# LightBoard.net
KiCad netlist of a schematic drawn in EAGLE
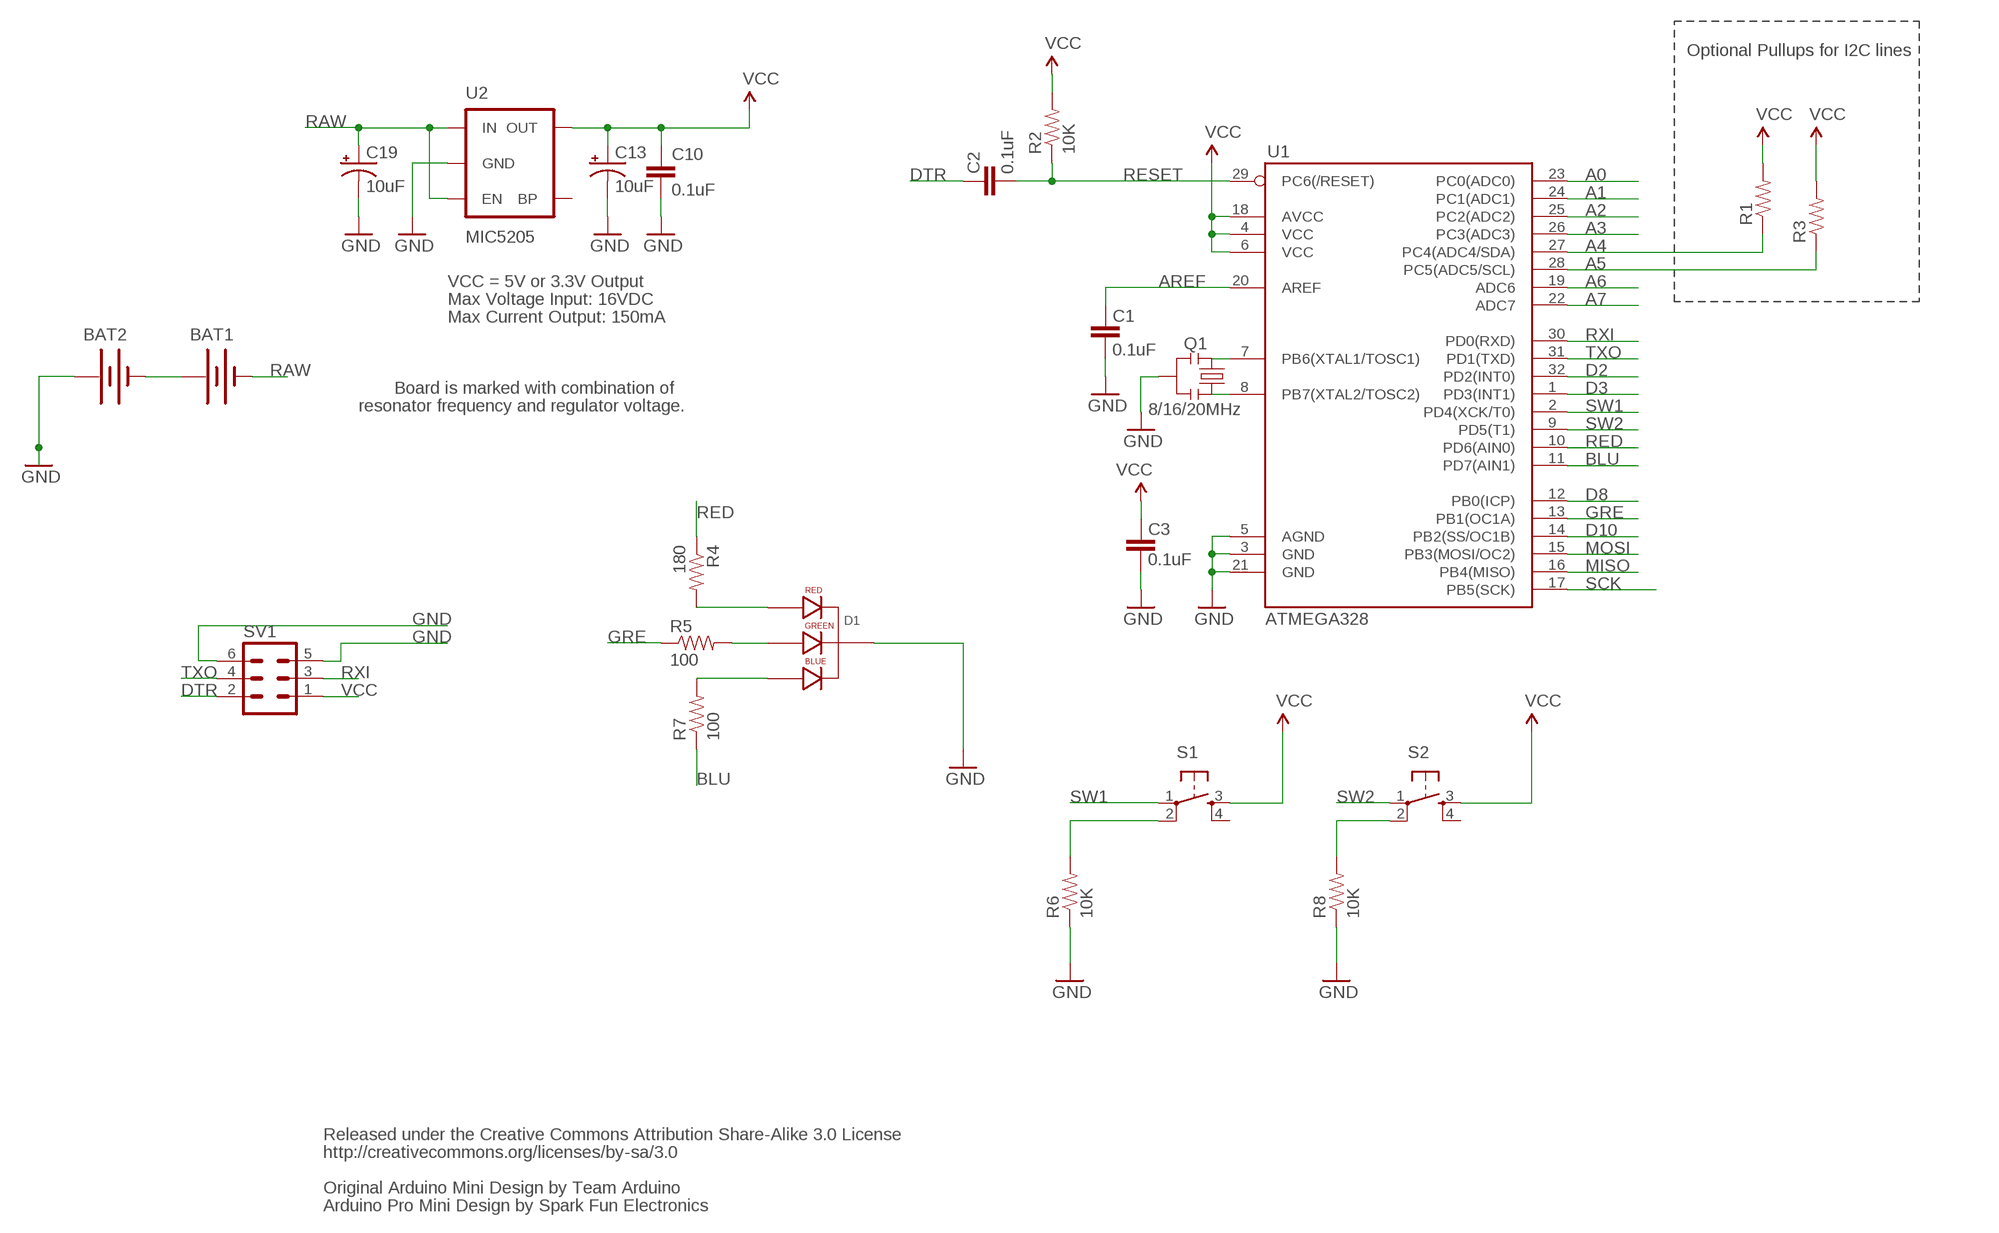
[diagram p0: schematic, sheet 1]

(export (version "E")
  (design (tool "Eeschema 10.0.6"))
  (components
    (comp (ref "BAT1")
      (value "BATTERY12MM")
      (footprint "eagle-import:BATTCON_12MM")
      (libsource (lib "eagle-import") (part "BATTERY12MM"))
    )
    (comp (ref "BAT2")
      (value "BATTERY12MM")
      (footprint "eagle-import:BATTCON_12MM")
      (libsource (lib "eagle-import") (part "BATTERY12MM"))
    )
    (comp (ref "C1")
      (value "0.1uF")
      (footprint "eagle-import:0402-CAP")
      (libsource (lib "eagle-import") (part "CAP0402-CAP"))
    )
    (comp (ref "C2")
      (value "0.1uF")
      (footprint "eagle-import:0402-CAP")
      (libsource (lib "eagle-import") (part "CAP0402-CAP"))
    )
    (comp (ref "C3")
      (value "0.1uF")
      (footprint "eagle-import:0402-CAP")
      (libsource (lib "eagle-import") (part "CAP0402-CAP"))
    )
    (comp (ref "C10")
      (value "0.1uF")
      (footprint "eagle-import:0402-CAP")
      (libsource (lib "eagle-import") (part "CAP0402-CAP"))
    )
    (comp (ref "C13")
      (value "10uF")
      (footprint "eagle-import:EIA3216")
      (libsource (lib "eagle-import") (part "CAP_POL1206"))
    )
    (comp (ref "C19")
      (value "10uF")
      (footprint "eagle-import:EIA3216")
      (libsource (lib "eagle-import") (part "CAP_POL1206"))
    )
    (comp (ref "D1")
      (value "LED-RGB-CC-THRUDIFFUSE")
      (footprint "eagle-import:LED-RGB-THRU")
      (libsource (lib "eagle-import") (part "LED-RGB-CC-THRUDIFFUSE"))
    )
    (comp (ref "Q1")
      (value "8/16/20MHz")
      (footprint "eagle-import:RESONATOR-SMD")
      (libsource (lib "eagle-import") (part "RESONATORSMD"))
    )
    (comp (ref "R1")
      (value "RESISTOR0402-RES")
      (footprint "eagle-import:0402-RES")
      (libsource (lib "eagle-import") (part "RESISTOR0402-RES"))
    )
    (comp (ref "R2")
      (value "10K")
      (footprint "eagle-import:0402-RES")
      (libsource (lib "eagle-import") (part "RESISTOR0402-RES"))
    )
    (comp (ref "R3")
      (value "RESISTOR0402-RES")
      (footprint "eagle-import:0402-RES")
      (libsource (lib "eagle-import") (part "RESISTOR0402-RES"))
    )
    (comp (ref "R4")
      (value "180")
      (footprint "eagle-import:0402-RES")
      (libsource (lib "eagle-import") (part "SparkFun-Passives_RESISTOR0402-RES"))
    )
    (comp (ref "R5")
      (value "100")
      (footprint "eagle-import:0402-RES")
      (libsource (lib "eagle-import") (part "SparkFun-Passives_RESISTOR0402-RES"))
    )
    (comp (ref "R6")
      (value "10K")
      (footprint "eagle-import:0402-RES")
      (libsource (lib "eagle-import") (part "SparkFun-Passives_RESISTOR0402-RES"))
    )
    (comp (ref "R7")
      (value "100")
      (footprint "eagle-import:0402-RES")
      (libsource (lib "eagle-import") (part "SparkFun-Passives_RESISTOR0402-RES"))
    )
    (comp (ref "R8")
      (value "10K")
      (footprint "eagle-import:0402-RES")
      (libsource (lib "eagle-import") (part "SparkFun-Passives_RESISTOR0402-RES"))
    )
    (comp (ref "S1")
      (value "TAC_SWITCHPTH")
      (footprint "eagle-import:TACTILE-PTH")
      (libsource (lib "eagle-import") (part "TAC_SWITCHPTH"))
    )
    (comp (ref "S2")
      (value "TAC_SWITCHPTH")
      (footprint "eagle-import:TACTILE-PTH")
      (libsource (lib "eagle-import") (part "TAC_SWITCHPTH"))
    )
    (comp (ref "SV1")
      (value "MA03-2")
      (footprint "eagle-import:MA03-2")
      (libsource (lib "eagle-import") (part "MA03-2"))
    )
    (comp (ref "U1")
      (value "ATMEGA328")
      (footprint "eagle-import:TQFP32-08")
      (libsource (lib "eagle-import") (part "ATMEGA168"))
    )
    (comp (ref "U2")
      (value "MIC5205")
      (footprint "eagle-import:SOT23-5")
      (libsource (lib "eagle-import") (part "V_REG_LDOSMD"))
    )
  )
  (nets
    (net (code "1") (name "/A0") (class "Default")
      (node (ref "U1") (pin "23") (pinfunction "PC0(ADC0)_23") (pintype "bidirectional"))
    )
    (net (code "2") (name "/A1") (class "Default")
      (node (ref "U1") (pin "24") (pinfunction "PC1(ADC1)_24") (pintype "bidirectional"))
    )
    (net (code "3") (name "/A2") (class "Default")
      (node (ref "U1") (pin "25") (pinfunction "PC2(ADC2)_25") (pintype "bidirectional"))
    )
    (net (code "4") (name "/A3") (class "Default")
      (node (ref "U1") (pin "26") (pinfunction "PC3(ADC3)_26") (pintype "bidirectional"))
    )
    (net (code "5") (name "/A4") (class "Default")
      (node (ref "R1") (pin "1") (pinfunction "1_1") (pintype "passive"))
      (node (ref "U1") (pin "27") (pinfunction "PC4(ADC4/SDA)_27") (pintype "bidirectional"))
    )
    (net (code "6") (name "/A5") (class "Default")
      (node (ref "R3") (pin "1") (pinfunction "1_1") (pintype "passive"))
      (node (ref "U1") (pin "28") (pinfunction "PC5(ADC5/SCL)_28") (pintype "bidirectional"))
    )
    (net (code "7") (name "/A6") (class "Default")
      (node (ref "U1") (pin "19") (pinfunction "ADC6_19") (pintype "bidirectional"))
    )
    (net (code "8") (name "/A7") (class "Default")
      (node (ref "U1") (pin "22") (pinfunction "ADC7_22") (pintype "bidirectional"))
    )
    (net (code "9") (name "/AREF") (class "Default")
      (node (ref "C1") (pin "2") (pinfunction "2_2") (pintype "passive"))
      (node (ref "U1") (pin "20") (pinfunction "AREF_20") (pintype "bidirectional"))
    )
    (net (code "10") (name "/BLU") (class "Default")
      (node (ref "R7") (pin "1") (pinfunction "1_1") (pintype "passive"))
      (node (ref "U1") (pin "11") (pinfunction "PD7(AIN1)_11") (pintype "bidirectional"))
    )
    (net (code "11") (name "/D2") (class "Default")
      (node (ref "U1") (pin "32") (pinfunction "PD2(INT0)_32") (pintype "bidirectional"))
    )
    (net (code "12") (name "/D3") (class "Default")
      (node (ref "U1") (pin "1") (pinfunction "PD3(INT1)_1") (pintype "bidirectional"))
    )
    (net (code "13") (name "/D8") (class "Default")
      (node (ref "U1") (pin "12") (pinfunction "PB0(ICP)_12") (pintype "bidirectional"))
    )
    (net (code "14") (name "/D10") (class "Default")
      (node (ref "U1") (pin "14") (pinfunction "PB2(SS/OC1B)_14") (pintype "bidirectional"))
    )
    (net (code "15") (name "/DTR") (class "Default")
      (node (ref "C2") (pin "2") (pinfunction "2_2") (pintype "passive"))
      (node (ref "SV1") (pin "2") (pinfunction "2_2") (pintype "passive"))
    )
    (net (code "16") (name "/GRE") (class "Default")
      (node (ref "R5") (pin "1") (pinfunction "1_1") (pintype "passive"))
      (node (ref "U1") (pin "13") (pinfunction "PB1(OC1A)_13") (pintype "bidirectional"))
    )
    (net (code "17") (name "/MISO") (class "Default")
      (node (ref "U1") (pin "16") (pinfunction "PB4(MISO)_16") (pintype "bidirectional"))
    )
    (net (code "18") (name "/MOSI") (class "Default")
      (node (ref "U1") (pin "15") (pinfunction "PB3(MOSI/OC2)_15") (pintype "bidirectional"))
    )
    (net (code "19") (name "/RAW") (class "Default")
      (node (ref "BAT1") (pin "GND") (pinfunction "-_GND") (pintype "power_in"))
      (node (ref "C19") (pin "A") (pinfunction "+_A") (pintype "passive"))
      (node (ref "U2") (pin "1") (pinfunction "IN_1") (pintype "input"))
      (node (ref "U2") (pin "3") (pinfunction "EN_3") (pintype "input"))
    )
    (net (code "20") (name "/RED") (class "Default")
      (node (ref "R4") (pin "1") (pinfunction "1_1") (pintype "passive"))
      (node (ref "U1") (pin "10") (pinfunction "PD6(AIN0)_10") (pintype "bidirectional"))
    )
    (net (code "21") (name "/RESET") (class "Default")
      (node (ref "C2") (pin "1") (pinfunction "1_1") (pintype "passive"))
      (node (ref "R2") (pin "1") (pinfunction "1_1") (pintype "passive"))
      (node (ref "U1") (pin "29") (pinfunction "PC6(/RESET)_29") (pintype "bidirectional"))
    )
    (net (code "22") (name "/RXI") (class "Default")
      (node (ref "SV1") (pin "3") (pinfunction "3_3") (pintype "passive"))
      (node (ref "U1") (pin "30") (pinfunction "PD0(RXD)_30") (pintype "bidirectional"))
    )
    (net (code "23") (name "/SCK") (class "Default")
      (node (ref "U1") (pin "17") (pinfunction "PB5(SCK)_17") (pintype "bidirectional"))
    )
    (net (code "24") (name "/SW1") (class "Default")
      (node (ref "S1") (pin "1") (pinfunction "1_1") (pintype "passive"))
      (node (ref "U1") (pin "2") (pinfunction "PD4(XCK/T0)_2") (pintype "bidirectional"))
    )
    (net (code "25") (name "/SW2") (class "Default")
      (node (ref "S2") (pin "1") (pinfunction "1_1") (pintype "passive"))
      (node (ref "U1") (pin "9") (pinfunction "PD5(T1)_9") (pintype "bidirectional"))
    )
    (net (code "26") (name "/TXO") (class "Default")
      (node (ref "SV1") (pin "4") (pinfunction "4_4") (pintype "passive"))
      (node (ref "U1") (pin "31") (pinfunction "PD1(TXD)_31") (pintype "bidirectional"))
    )
    (net (code "27") (name "GND") (class "Default")
      (node (ref "BAT2") (pin "PWR@1") (pinfunction "+_PWR@1") (pintype "power_in"))
      (node (ref "C1") (pin "1") (pinfunction "1_1") (pintype "passive"))
      (node (ref "C10") (pin "2") (pinfunction "2_2") (pintype "passive"))
      (node (ref "C13") (pin "C") (pinfunction "-_C") (pintype "passive"))
      (node (ref "C19") (pin "C") (pinfunction "-_C") (pintype "passive"))
      (node (ref "C3") (pin "1") (pinfunction "1_1") (pintype "passive"))
      (node (ref "D1") (pin "2") (pinfunction "CATHODE_2") (pintype "bidirectional"))
      (node (ref "Q1") (pin "2") (pinfunction "2_2") (pintype "passive"))
      (node (ref "R6") (pin "1") (pinfunction "1_1") (pintype "passive"))
      (node (ref "R8") (pin "1") (pinfunction "1_1") (pintype "passive"))
      (node (ref "SV1") (pin "5") (pinfunction "5_5") (pintype "passive"))
      (node (ref "SV1") (pin "6") (pinfunction "6_6") (pintype "passive"))
      (node (ref "U1") (pin "21") (pinfunction "GND_21") (pintype "bidirectional"))
      (node (ref "U1") (pin "3") (pinfunction "GND_3") (pintype "bidirectional"))
      (node (ref "U1") (pin "5") (pinfunction "AGND_5") (pintype "bidirectional"))
      (node (ref "U2") (pin "2") (pinfunction "GND_2") (pintype "input"))
    )
    (net (code "28") (name "Net-(BAT1-+)") (class "Default")
      (node (ref "BAT1") (pin "PWR@1") (pinfunction "+_PWR@1") (pintype "power_in"))
      (node (ref "BAT2") (pin "GND") (pinfunction "-_GND") (pintype "power_in"))
    )
    (net (code "29") (name "Net-(D1-BLUE_CATHODE)") (class "Default")
      (node (ref "D1") (pin "4") (pinfunction "BLUE_CATHODE_4") (pintype "bidirectional"))
      (node (ref "R7") (pin "2") (pinfunction "2_2") (pintype "passive"))
    )
    (net (code "30") (name "Net-(D1-GREEN_CATHODE)") (class "Default")
      (node (ref "D1") (pin "3") (pinfunction "GREEN_CATHODE_3") (pintype "bidirectional"))
      (node (ref "R5") (pin "2") (pinfunction "2_2") (pintype "passive"))
    )
    (net (code "31") (name "Net-(D1-RED_CATHODE)") (class "Default")
      (node (ref "D1") (pin "1") (pinfunction "RED_CATHODE_1") (pintype "bidirectional"))
      (node (ref "R4") (pin "2") (pinfunction "2_2") (pintype "passive"))
    )
    (net (code "32") (name "Net-(R6-Pad2)") (class "Default")
      (node (ref "R6") (pin "2") (pinfunction "2_2") (pintype "passive"))
      (node (ref "S1") (pin "2") (pinfunction "2_2") (pintype "passive"))
    )
    (net (code "33") (name "Net-(R8-Pad2)") (class "Default")
      (node (ref "R8") (pin "2") (pinfunction "2_2") (pintype "passive"))
      (node (ref "S2") (pin "2") (pinfunction "2_2") (pintype "passive"))
    )
    (net (code "34") (name "Net-(U1-PB6(XTAL1{slash}TOSC1))") (class "Default")
      (node (ref "Q1") (pin "3") (pinfunction "3_3") (pintype "passive"))
      (node (ref "U1") (pin "7") (pinfunction "PB6(XTAL1/TOSC1)_7") (pintype "bidirectional"))
    )
    (net (code "35") (name "Net-(U1-PB7(XTAL2{slash}TOSC2))") (class "Default")
      (node (ref "Q1") (pin "1") (pinfunction "1_1") (pintype "passive"))
      (node (ref "U1") (pin "8") (pinfunction "PB7(XTAL2/TOSC2)_8") (pintype "bidirectional"))
    )
    (net (code "36") (name "VCC") (class "Default")
      (node (ref "C10") (pin "1") (pinfunction "1_1") (pintype "passive"))
      (node (ref "C13") (pin "A") (pinfunction "+_A") (pintype "passive"))
      (node (ref "C3") (pin "2") (pinfunction "2_2") (pintype "passive"))
      (node (ref "R1") (pin "2") (pinfunction "2_2") (pintype "passive"))
      (node (ref "R2") (pin "2") (pinfunction "2_2") (pintype "passive"))
      (node (ref "R3") (pin "2") (pinfunction "2_2") (pintype "passive"))
      (node (ref "S1") (pin "3") (pinfunction "3_3") (pintype "passive"))
      (node (ref "S2") (pin "3") (pinfunction "3_3") (pintype "passive"))
      (node (ref "SV1") (pin "1") (pinfunction "1_1") (pintype "passive"))
      (node (ref "U1") (pin "18") (pinfunction "AVCC_18") (pintype "bidirectional"))
      (node (ref "U1") (pin "4") (pinfunction "VCC_4") (pintype "bidirectional"))
      (node (ref "U1") (pin "6") (pinfunction "VCC_6") (pintype "bidirectional"))
      (node (ref "U2") (pin "5") (pinfunction "OUT_5") (pintype "passive"))
    )
    (net (code "37") (name "unconnected-(S1-Pad4)") (class "Default")
      (node (ref "S1") (pin "4") (pinfunction "4_4") (pintype "passive"))
    )
    (net (code "38") (name "unconnected-(S2-Pad4)") (class "Default")
      (node (ref "S2") (pin "4") (pinfunction "4_4") (pintype "passive"))
    )
    (net (code "39") (name "unconnected-(U2-BP-Pad4)") (class "Default")
      (node (ref "U2") (pin "4") (pinfunction "BP_4") (pintype "input"))
    )
  )
)
